# digital_input_shifter.net
KiCad netlist of a schematic drawn in Altium Designer
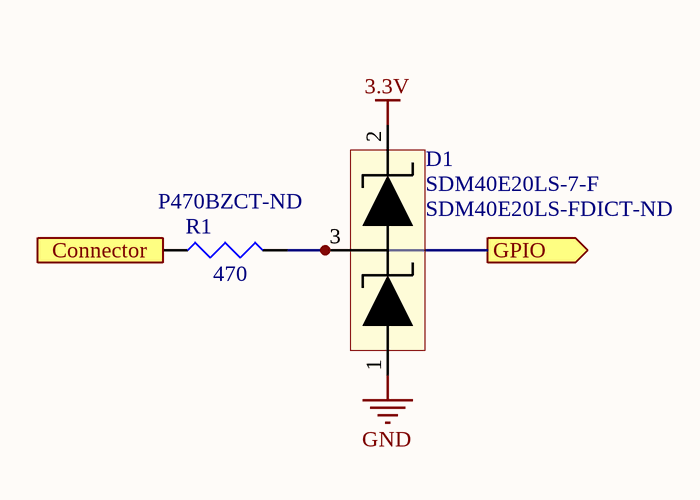
[diagram p0: digital_input_shifter.SchDoc]

(export (version "E")
  (design (tool "Eeschema 10.0.6"))
  (components
    (comp (ref "D1")
      (value "SDM40E20LS-7-F")
      (footprint "Miscellaneous Devices:SOT-23_N")
      (description "SDM40E20LS-7-F schottky series pair diode.")
      (fields (field (name "SUPPLIER PART NUMBER 1") "SDM40E20LS-FDICT-ND"))
      (libsource (lib "altium-import") (part "root_0_SDM40E20LS-7-F_"))
    )
    (comp (ref "R1")
      (value "470")
      (footprint "J1-0603")
      (description "Resistor")
      (fields
        (field (name "SUPPLIER PART NUMBER 1") "P470BZCT-ND")
        (field (name "Comment") "Res3")
        (field (name "PUBLISHER") "Altium Limited")
      )
      (libsource (lib "Miscellaneous Devices") (part "Res3"))
    )
  )
  (nets
    (net (code "1") (name "/Connector") (class "Default")
      (node (ref "R1") (pin "1") (pinfunction "1_1") (pintype "passive"))
    )
    (net (code "2") (name "/GPIO") (class "Default")
      (node (ref "D1") (pin "3") (pinfunction "3_3") (pintype "passive"))
      (node (ref "R1") (pin "2") (pinfunction "2_2") (pintype "passive"))
    )
    (net (code "3") (name "3.3V") (class "Default")
      (node (ref "D1") (pin "2") (pinfunction "2_2") (pintype "passive"))
    )
    (net (code "4") (name "GND") (class "Default")
      (node (ref "D1") (pin "1") (pinfunction "1_1") (pintype "passive"))
    )
  )
)
